# H-API_SVF.net
KiCad netlist of a schematic drawn in EAGLE
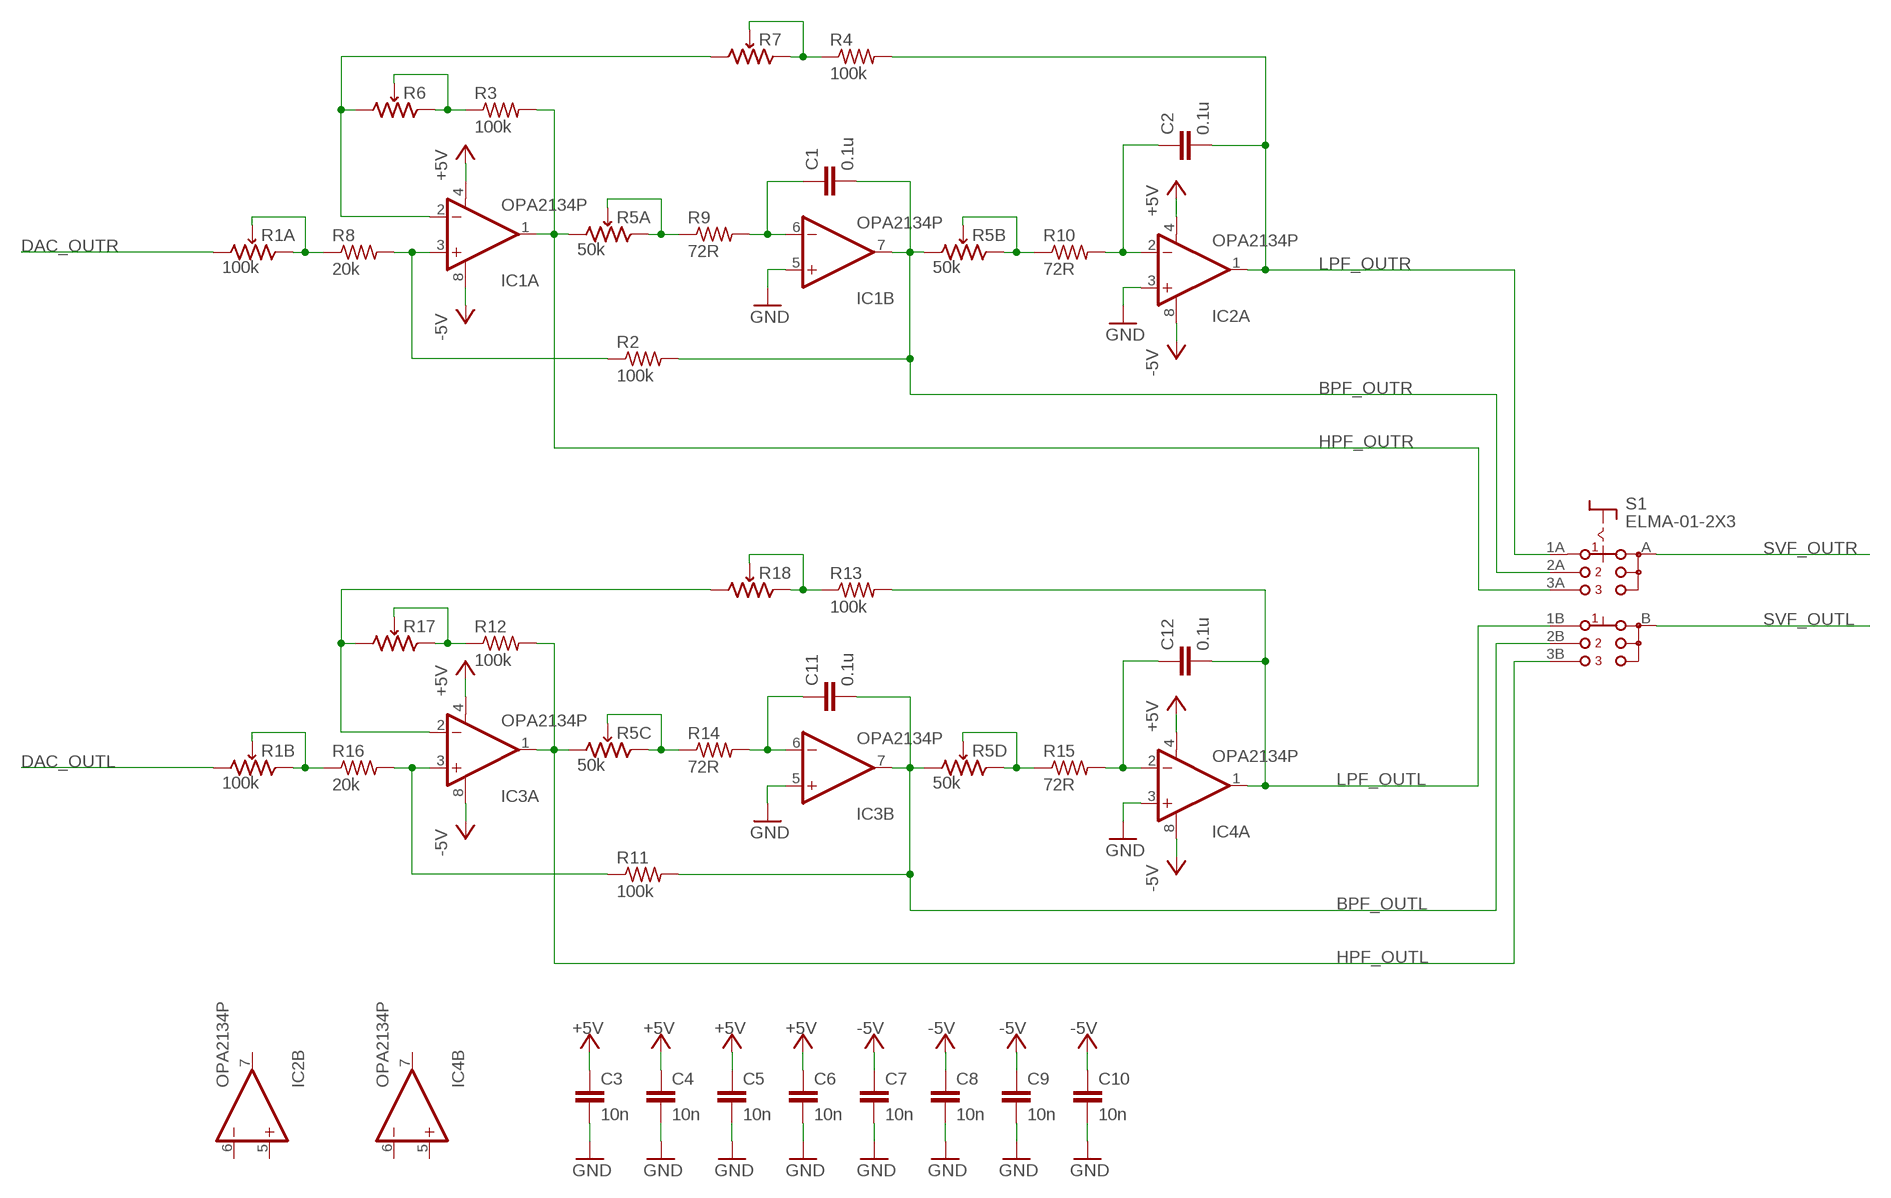
[diagram p0: schematic, sheet 1]

(export (version "E")
  (design (tool "Eeschema 10.0.6"))
  (components
    (comp (ref "C1")
      (value "0.1u")
      (footprint "eagle-import:C0805")
      (libsource (lib "eagle-import") (part "C-EUC0805"))
    )
    (comp (ref "C2")
      (value "0.1u")
      (footprint "eagle-import:C0805")
      (libsource (lib "eagle-import") (part "C-EUC0805"))
    )
    (comp (ref "C3")
      (value "10n")
      (footprint "eagle-import:C0805")
      (libsource (lib "eagle-import") (part "C-EUC0805"))
    )
    (comp (ref "C4")
      (value "10n")
      (footprint "eagle-import:C0805")
      (libsource (lib "eagle-import") (part "C-EUC0805"))
    )
    (comp (ref "C5")
      (value "10n")
      (footprint "eagle-import:C0805")
      (libsource (lib "eagle-import") (part "C-EUC0805"))
    )
    (comp (ref "C6")
      (value "10n")
      (footprint "eagle-import:C0805")
      (libsource (lib "eagle-import") (part "C-EUC0805"))
    )
    (comp (ref "C7")
      (value "10n")
      (footprint "eagle-import:C0805")
      (libsource (lib "eagle-import") (part "C-EUC0805"))
    )
    (comp (ref "C8")
      (value "10n")
      (footprint "eagle-import:C0805")
      (libsource (lib "eagle-import") (part "C-EUC0805"))
    )
    (comp (ref "C9")
      (value "10n")
      (footprint "eagle-import:C0805")
      (libsource (lib "eagle-import") (part "C-EUC0805"))
    )
    (comp (ref "C10")
      (value "10n")
      (footprint "eagle-import:C0805")
      (libsource (lib "eagle-import") (part "C-EUC0805"))
    )
    (comp (ref "C11")
      (value "0.1u")
      (footprint "eagle-import:C0805")
      (libsource (lib "eagle-import") (part "C-EUC0805"))
    )
    (comp (ref "C12")
      (value "0.1u")
      (footprint "eagle-import:C0805")
      (libsource (lib "eagle-import") (part "C-EUC0805"))
    )
    (comp (ref "IC1")
      (value "OPA2134P")
      (footprint "eagle-import:DIL08")
      (fields (field (name "MF") "TEXAS INSTRUMENTS") (field (name "MPN") "OPA2134PA"))
      (libsource (lib "eagle-import") (part "OPA2134P"))
    )
    (comp (ref "IC2")
      (value "OPA2134P")
      (footprint "eagle-import:DIL08")
      (fields (field (name "MF") "TEXAS INSTRUMENTS") (field (name "MPN") "OPA2134PA"))
      (libsource (lib "eagle-import") (part "OPA2134P"))
    )
    (comp (ref "IC3")
      (value "OPA2134P")
      (footprint "eagle-import:DIL08")
      (fields (field (name "MF") "TEXAS INSTRUMENTS") (field (name "MPN") "OPA2134PA"))
      (libsource (lib "eagle-import") (part "OPA2134P"))
    )
    (comp (ref "IC4")
      (value "OPA2134P")
      (footprint "eagle-import:DIL08")
      (fields (field (name "MF") "TEXAS INSTRUMENTS") (field (name "MPN") "OPA2134PA"))
      (libsource (lib "eagle-import") (part "OPA2134P"))
    )
    (comp (ref "R1")
      (value "100k")
      (footprint "eagle-import:POT2-SW")
      (libsource (lib "eagle-import") (part "PTR902-2015F-C104"))
    )
    (comp (ref "R2")
      (value "100k")
      (footprint "eagle-import:VMTA55")
      (libsource (lib "eagle-import") (part "R-US_VMTA55"))
    )
    (comp (ref "R3")
      (value "100k")
      (footprint "eagle-import:VMTA55")
      (libsource (lib "eagle-import") (part "R-US_VMTA55"))
    )
    (comp (ref "R4")
      (value "100k")
      (footprint "eagle-import:VMTA55")
      (libsource (lib "eagle-import") (part "R-US_VMTA55"))
    )
    (comp (ref "R5")
      (value "50k")
      (footprint "eagle-import:POT4")
      (libsource (lib "eagle-import") (part "PTD904-2015K-C503"))
    )
    (comp (ref "R6")
      (value "TRIM-POT")
      (footprint "eagle-import:CT6")
      (libsource (lib "eagle-import") (part "TRIM-POT"))
    )
    (comp (ref "R7")
      (value "TRIM-POT")
      (footprint "eagle-import:CT6")
      (libsource (lib "eagle-import") (part "TRIM-POT"))
    )
    (comp (ref "R8")
      (value "20k")
      (footprint "eagle-import:VMTA55")
      (libsource (lib "eagle-import") (part "R-US_VMTA55"))
    )
    (comp (ref "R9")
      (value "72R")
      (footprint "eagle-import:VMTA55")
      (libsource (lib "eagle-import") (part "R-US_VMTA55"))
    )
    (comp (ref "R10")
      (value "72R")
      (footprint "eagle-import:VMTA55")
      (libsource (lib "eagle-import") (part "R-US_VMTA55"))
    )
    (comp (ref "R11")
      (value "100k")
      (footprint "eagle-import:VMTA55")
      (libsource (lib "eagle-import") (part "R-US_VMTA55"))
    )
    (comp (ref "R12")
      (value "100k")
      (footprint "eagle-import:VMTA55")
      (libsource (lib "eagle-import") (part "R-US_VMTA55"))
    )
    (comp (ref "R13")
      (value "100k")
      (footprint "eagle-import:VMTA55")
      (libsource (lib "eagle-import") (part "R-US_VMTA55"))
    )
    (comp (ref "R14")
      (value "72R")
      (footprint "eagle-import:VMTA55")
      (libsource (lib "eagle-import") (part "R-US_VMTA55"))
    )
    (comp (ref "R15")
      (value "72R")
      (footprint "eagle-import:VMTA55")
      (libsource (lib "eagle-import") (part "R-US_VMTA55"))
    )
    (comp (ref "R16")
      (value "20k")
      (footprint "eagle-import:VMTA55")
      (libsource (lib "eagle-import") (part "R-US_VMTA55"))
    )
    (comp (ref "R17")
      (value "TRIM-POT")
      (footprint "eagle-import:CT6")
      (libsource (lib "eagle-import") (part "TRIM-POT"))
    )
    (comp (ref "R18")
      (value "TRIM-POT")
      (footprint "eagle-import:CT6")
      (libsource (lib "eagle-import") (part "TRIM-POT"))
    )
    (comp (ref "S1")
      (value "ELMA-01-2X3")
      (footprint "eagle-import:ELMA-01-2X3")
      (libsource (lib "eagle-import") (part "ELMA-01-2X3"))
    )
  )
  (nets
    (net (code "1") (name "+5V") (class "Default")
      (node (ref "C3") (pin "1") (pinfunction "1_1") (pintype "passive"))
      (node (ref "C4") (pin "1") (pinfunction "1_1") (pintype "passive"))
      (node (ref "C5") (pin "1") (pinfunction "1_1") (pintype "passive"))
      (node (ref "C6") (pin "1") (pinfunction "1_1") (pintype "passive"))
      (node (ref "IC1") (pin "4") (pinfunction "V-_4") (pintype "power_in"))
      (node (ref "IC2") (pin "4") (pinfunction "V-_4") (pintype "power_in"))
      (node (ref "IC3") (pin "4") (pinfunction "V-_4") (pintype "power_in"))
      (node (ref "IC4") (pin "4") (pinfunction "V-_4") (pintype "power_in"))
    )
    (net (code "2") (name "-5V") (class "Default")
      (node (ref "C10") (pin "1") (pinfunction "1_1") (pintype "passive"))
      (node (ref "C7") (pin "1") (pinfunction "1_1") (pintype "passive"))
      (node (ref "C8") (pin "1") (pinfunction "1_1") (pintype "passive"))
      (node (ref "C9") (pin "1") (pinfunction "1_1") (pintype "passive"))
      (node (ref "IC1") (pin "8") (pinfunction "V+_8") (pintype "power_in"))
      (node (ref "IC2") (pin "8") (pinfunction "V+_8") (pintype "power_in"))
      (node (ref "IC3") (pin "8") (pinfunction "V+_8") (pintype "power_in"))
      (node (ref "IC4") (pin "8") (pinfunction "V+_8") (pintype "power_in"))
    )
    (net (code "3") (name "/BPF_OUTL") (class "Default")
      (node (ref "C11") (pin "2") (pinfunction "2_2") (pintype "passive"))
      (node (ref "IC3") (pin "7") (pinfunction "OUT_7") (pintype "output"))
      (node (ref "R11") (pin "2") (pinfunction "2_2") (pintype "passive"))
      (node (ref "R5") (pin "4A") (pinfunction "1_4A") (pintype "bidirectional"))
      (node (ref "S1") (pin "2B") (pinfunction "B2_2B") (pintype "passive"))
    )
    (net (code "4") (name "/BPF_OUTR") (class "Default")
      (node (ref "C1") (pin "2") (pinfunction "2_2") (pintype "passive"))
      (node (ref "IC1") (pin "7") (pinfunction "OUT_7") (pintype "output"))
      (node (ref "R2") (pin "2") (pinfunction "2_2") (pintype "passive"))
      (node (ref "R5") (pin "2A") (pinfunction "1_2A") (pintype "bidirectional"))
      (node (ref "S1") (pin "2A") (pinfunction "A2_2A") (pintype "passive"))
    )
    (net (code "5") (name "/DAC_OUTL") (class "Default")
      (node (ref "R1") (pin "2A") (pinfunction "1_2A") (pintype "bidirectional"))
    )
    (net (code "6") (name "/DAC_OUTR") (class "Default")
      (node (ref "R1") (pin "1A") (pinfunction "1_1A") (pintype "bidirectional"))
    )
    (net (code "7") (name "/HPF_OUTL") (class "Default")
      (node (ref "IC3") (pin "1") (pinfunction "OUT_1") (pintype "output"))
      (node (ref "R12") (pin "2") (pinfunction "2_2") (pintype "passive"))
      (node (ref "R5") (pin "3A") (pinfunction "1_3A") (pintype "bidirectional"))
      (node (ref "S1") (pin "3B") (pinfunction "B3_3B") (pintype "passive"))
    )
    (net (code "8") (name "/HPF_OUTR") (class "Default")
      (node (ref "IC1") (pin "1") (pinfunction "OUT_1") (pintype "output"))
      (node (ref "R3") (pin "2") (pinfunction "2_2") (pintype "passive"))
      (node (ref "R5") (pin "1A") (pinfunction "1_1A") (pintype "bidirectional"))
      (node (ref "S1") (pin "3A") (pinfunction "A3_3A") (pintype "passive"))
    )
    (net (code "9") (name "/LPF_OUTL") (class "Default")
      (node (ref "C12") (pin "2") (pinfunction "2_2") (pintype "passive"))
      (node (ref "IC4") (pin "1") (pinfunction "OUT_1") (pintype "output"))
      (node (ref "R13") (pin "2") (pinfunction "2_2") (pintype "passive"))
      (node (ref "S1") (pin "1B") (pinfunction "B1_1B") (pintype "passive"))
    )
    (net (code "10") (name "/LPF_OUTR") (class "Default")
      (node (ref "C2") (pin "2") (pinfunction "2_2") (pintype "passive"))
      (node (ref "IC2") (pin "1") (pinfunction "OUT_1") (pintype "output"))
      (node (ref "R4") (pin "2") (pinfunction "2_2") (pintype "passive"))
      (node (ref "S1") (pin "1A") (pinfunction "A1_1A") (pintype "passive"))
    )
    (net (code "11") (name "/SVF_OUTL") (class "Default")
      (node (ref "S1") (pin "B") (pinfunction "B_B") (pintype "passive"))
    )
    (net (code "12") (name "/SVF_OUTR") (class "Default")
      (node (ref "S1") (pin "A") (pinfunction "A_A") (pintype "passive"))
    )
    (net (code "13") (name "GND") (class "Default")
      (node (ref "C10") (pin "2") (pinfunction "2_2") (pintype "passive"))
      (node (ref "C3") (pin "2") (pinfunction "2_2") (pintype "passive"))
      (node (ref "C4") (pin "2") (pinfunction "2_2") (pintype "passive"))
      (node (ref "C5") (pin "2") (pinfunction "2_2") (pintype "passive"))
      (node (ref "C6") (pin "2") (pinfunction "2_2") (pintype "passive"))
      (node (ref "C7") (pin "2") (pinfunction "2_2") (pintype "passive"))
      (node (ref "C8") (pin "2") (pinfunction "2_2") (pintype "passive"))
      (node (ref "C9") (pin "2") (pinfunction "2_2") (pintype "passive"))
      (node (ref "IC1") (pin "5") (pinfunction "+IN_5") (pintype "input"))
      (node (ref "IC2") (pin "3") (pinfunction "+IN_3") (pintype "input"))
      (node (ref "IC3") (pin "5") (pinfunction "+IN_5") (pintype "input"))
      (node (ref "IC4") (pin "3") (pinfunction "+IN_3") (pintype "input"))
    )
    (net (code "14") (name "Net-(IC1A-+IN)") (class "Default")
      (node (ref "IC1") (pin "3") (pinfunction "+IN_3") (pintype "input"))
      (node (ref "R2") (pin "1") (pinfunction "1_1") (pintype "passive"))
      (node (ref "R8") (pin "2") (pinfunction "2_2") (pintype "passive"))
    )
    (net (code "15") (name "Net-(IC1A--IN)") (class "Default")
      (node (ref "IC1") (pin "2") (pinfunction "-IN_2") (pintype "input"))
      (node (ref "R6") (pin "A") (pinfunction "1_A") (pintype "bidirectional"))
      (node (ref "R7") (pin "A") (pinfunction "1_A") (pintype "bidirectional"))
    )
    (net (code "16") (name "Net-(IC1B--IN)") (class "Default")
      (node (ref "C1") (pin "1") (pinfunction "1_1") (pintype "passive"))
      (node (ref "IC1") (pin "6") (pinfunction "-IN_6") (pintype "input"))
      (node (ref "R9") (pin "2") (pinfunction "2_2") (pintype "passive"))
    )
    (net (code "17") (name "Net-(IC2A--IN)") (class "Default")
      (node (ref "C2") (pin "1") (pinfunction "1_1") (pintype "passive"))
      (node (ref "IC2") (pin "2") (pinfunction "-IN_2") (pintype "input"))
      (node (ref "R10") (pin "2") (pinfunction "2_2") (pintype "passive"))
    )
    (net (code "18") (name "Net-(IC3A-+IN)") (class "Default")
      (node (ref "IC3") (pin "3") (pinfunction "+IN_3") (pintype "input"))
      (node (ref "R11") (pin "1") (pinfunction "1_1") (pintype "passive"))
      (node (ref "R16") (pin "2") (pinfunction "2_2") (pintype "passive"))
    )
    (net (code "19") (name "Net-(IC3A--IN)") (class "Default")
      (node (ref "IC3") (pin "2") (pinfunction "-IN_2") (pintype "input"))
      (node (ref "R17") (pin "A") (pinfunction "1_A") (pintype "bidirectional"))
      (node (ref "R18") (pin "A") (pinfunction "1_A") (pintype "bidirectional"))
    )
    (net (code "20") (name "Net-(IC3B--IN)") (class "Default")
      (node (ref "C11") (pin "1") (pinfunction "1_1") (pintype "passive"))
      (node (ref "IC3") (pin "6") (pinfunction "-IN_6") (pintype "input"))
      (node (ref "R14") (pin "2") (pinfunction "2_2") (pintype "passive"))
    )
    (net (code "21") (name "Net-(IC4A--IN)") (class "Default")
      (node (ref "C12") (pin "1") (pinfunction "1_1") (pintype "passive"))
      (node (ref "IC4") (pin "2") (pinfunction "-IN_2") (pintype "input"))
      (node (ref "R15") (pin "2") (pinfunction "2_2") (pintype "passive"))
    )
    (net (code "22") (name "Net-(R1B-2)") (class "Default")
      (node (ref "R1") (pin "1E") (pinfunction "3_1E") (pintype "bidirectional"))
      (node (ref "R1") (pin "1S") (pinfunction "2_1S") (pintype "bidirectional"))
      (node (ref "R8") (pin "1") (pinfunction "1_1") (pintype "passive"))
    )
    (net (code "23") (name "Net-(R1C-2)") (class "Default")
      (node (ref "R1") (pin "2E") (pinfunction "3_2E") (pintype "bidirectional"))
      (node (ref "R1") (pin "2S") (pinfunction "2_2S") (pintype "bidirectional"))
      (node (ref "R16") (pin "1") (pinfunction "1_1") (pintype "passive"))
    )
    (net (code "24") (name "Net-(R5A-2)") (class "Default")
      (node (ref "R5") (pin "1E") (pinfunction "3_1E") (pintype "bidirectional"))
      (node (ref "R5") (pin "1S") (pinfunction "2_1S") (pintype "bidirectional"))
      (node (ref "R9") (pin "1") (pinfunction "1_1") (pintype "passive"))
    )
    (net (code "25") (name "Net-(R5B-2)") (class "Default")
      (node (ref "R10") (pin "1") (pinfunction "1_1") (pintype "passive"))
      (node (ref "R5") (pin "2E") (pinfunction "3_2E") (pintype "bidirectional"))
      (node (ref "R5") (pin "2S") (pinfunction "2_2S") (pintype "bidirectional"))
    )
    (net (code "26") (name "Net-(R5C-2)") (class "Default")
      (node (ref "R14") (pin "1") (pinfunction "1_1") (pintype "passive"))
      (node (ref "R5") (pin "3E") (pinfunction "3_3E") (pintype "bidirectional"))
      (node (ref "R5") (pin "3S") (pinfunction "2_3S") (pintype "bidirectional"))
    )
    (net (code "27") (name "Net-(R5D-2)") (class "Default")
      (node (ref "R15") (pin "1") (pinfunction "1_1") (pintype "passive"))
      (node (ref "R5") (pin "4E") (pinfunction "3_4E") (pintype "bidirectional"))
      (node (ref "R5") (pin "4S") (pinfunction "2_4S") (pintype "bidirectional"))
    )
    (net (code "28") (name "Net-(R6-2)") (class "Default")
      (node (ref "R3") (pin "1") (pinfunction "1_1") (pintype "passive"))
      (node (ref "R6") (pin "E") (pinfunction "3_E") (pintype "bidirectional"))
      (node (ref "R6") (pin "S") (pinfunction "2_S") (pintype "bidirectional"))
    )
    (net (code "29") (name "Net-(R7-2)") (class "Default")
      (node (ref "R4") (pin "1") (pinfunction "1_1") (pintype "passive"))
      (node (ref "R7") (pin "E") (pinfunction "3_E") (pintype "bidirectional"))
      (node (ref "R7") (pin "S") (pinfunction "2_S") (pintype "bidirectional"))
    )
    (net (code "30") (name "Net-(R17-2)") (class "Default")
      (node (ref "R12") (pin "1") (pinfunction "1_1") (pintype "passive"))
      (node (ref "R17") (pin "E") (pinfunction "3_E") (pintype "bidirectional"))
      (node (ref "R17") (pin "S") (pinfunction "2_S") (pintype "bidirectional"))
    )
    (net (code "31") (name "Net-(R18-2)") (class "Default")
      (node (ref "R13") (pin "1") (pinfunction "1_1") (pintype "passive"))
      (node (ref "R18") (pin "E") (pinfunction "3_E") (pintype "bidirectional"))
      (node (ref "R18") (pin "S") (pinfunction "2_S") (pintype "bidirectional"))
    )
    (net (code "32") (name "unconnected-(IC2B-+IN-Pad5)") (class "Default")
      (node (ref "IC2") (pin "5") (pinfunction "+IN_5") (pintype "input"))
    )
    (net (code "33") (name "unconnected-(IC2B--IN-Pad6)") (class "Default")
      (node (ref "IC2") (pin "6") (pinfunction "-IN_6") (pintype "input"))
    )
    (net (code "34") (name "unconnected-(IC2B-OUT-Pad7)") (class "Default")
      (node (ref "IC2") (pin "7") (pinfunction "OUT_7") (pintype "output"))
    )
    (net (code "35") (name "unconnected-(IC4B-+IN-Pad5)") (class "Default")
      (node (ref "IC4") (pin "5") (pinfunction "+IN_5") (pintype "input"))
    )
    (net (code "36") (name "unconnected-(IC4B--IN-Pad6)") (class "Default")
      (node (ref "IC4") (pin "6") (pinfunction "-IN_6") (pintype "input"))
    )
    (net (code "37") (name "unconnected-(IC4B-OUT-Pad7)") (class "Default")
      (node (ref "IC4") (pin "7") (pinfunction "OUT_7") (pintype "output"))
    )
  )
)
